# 1S_BATTERY_CHARGER_SCH.net
KiCad netlist of a schematic drawn in Altium Designer
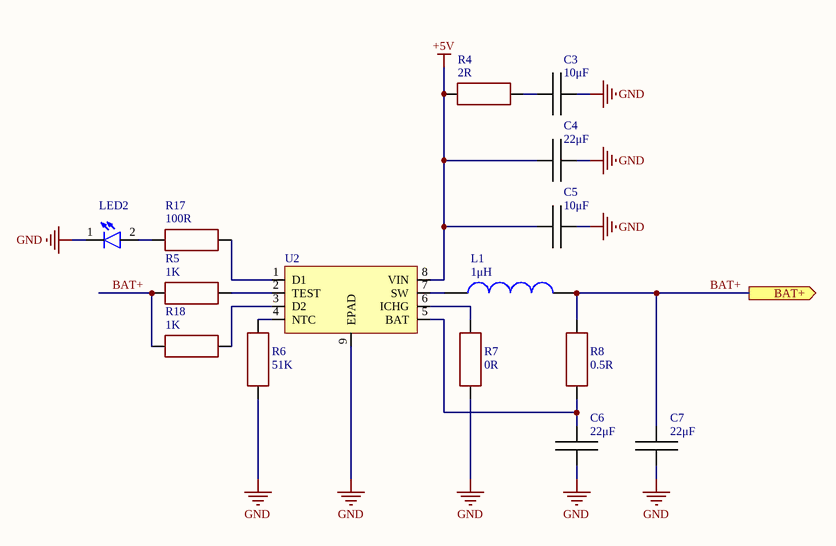
[diagram p0: 1S_BATTERY_CHARGER_SCH.SchDoc]

(export (version "E")
  (design (tool "Eeschema 10.0.6"))
  (components
    (comp (ref "C3")
      (value "10μF")
      (footprint "CAP: 0603")
      (fields (field (name "VOLTAGE") "??V") (field (name "Comment") "Cap_0603"))
      (libsource (lib "capacitor") (part "Cap_0603"))
    )
    (comp (ref "C4")
      (value "22μF")
      (footprint "CAP: 0603")
      (fields (field (name "VOLTAGE") "??V") (field (name "Comment") "Cap_0603"))
      (libsource (lib "capacitor") (part "Cap_0603"))
    )
    (comp (ref "C5")
      (value "10μF")
      (footprint "CAP: 0603")
      (fields (field (name "VOLTAGE") "??V") (field (name "Comment") "Cap_0603"))
      (libsource (lib "capacitor") (part "Cap_0603"))
    )
    (comp (ref "C6")
      (value "22μF")
      (footprint "CAP: 0603")
      (fields (field (name "VOLTAGE") "??V") (field (name "Comment") "Cap_0603"))
      (libsource (lib "capacitor") (part "Cap_0603"))
    )
    (comp (ref "C7")
      (value "22μF")
      (footprint "CAP: 0603")
      (fields (field (name "VOLTAGE") "??V") (field (name "Comment") "Cap_0603"))
      (libsource (lib "capacitor") (part "Cap_0603"))
    )
    (comp (ref "L1")
      (value "1μH")
      (footprint "CDRH74")
      (description "SMD Power Inductor")
      (fields (field (name "MANUFACTURER") "SUMIDA") (field (name "Comment") "CDRH74"))
      (libsource (lib "MY_INT_LIB") (part "CDRH74"))
    )
    (comp (ref "LED2")
      (value "LED_0603")
      (footprint "LED_0603")
      (libsource (lib "MY_INT_LIB") (part "LED_0603"))
    )
    (comp (ref "R4")
      (value "2R")
      (footprint "RES: 0603")
      (fields (field (name "TOLERANCE") "±5%") (field (name "Comment") "Resistor_0603"))
      (libsource (lib "") (part "Resistor_0603_1"))
    )
    (comp (ref "R5")
      (value "1K")
      (footprint "RES: 0603")
      (fields (field (name "TOLERANCE") "±5%") (field (name "Comment") "Resistor_0603"))
      (libsource (lib "resistor") (part "Resistor_0603"))
    )
    (comp (ref "R6")
      (value "51K")
      (footprint "RES: 0603")
      (fields (field (name "TOLERANCE") "±5%") (field (name "Comment") "Resistor_0603"))
      (libsource (lib "") (part "Resistor_0603_1"))
    )
    (comp (ref "R7")
      (value "0R")
      (footprint "RES: 0603")
      (fields (field (name "TOLERANCE") "±5%") (field (name "Comment") "Resistor_0603"))
      (libsource (lib "") (part "Resistor_0603_2"))
    )
    (comp (ref "R8")
      (value "0.5R")
      (footprint "RES: 0603")
      (fields (field (name "TOLERANCE") "±5%") (field (name "Comment") "Resistor_0603"))
      (libsource (lib "") (part "Resistor_0603_1"))
    )
    (comp (ref "R17")
      (value "100R")
      (footprint "RES: 0603")
      (fields (field (name "TOLERANCE") "±5%") (field (name "Comment") "Resistor_0603"))
      (libsource (lib "") (part "Resistor_0603_1"))
    )
    (comp (ref "R18")
      (value "1K")
      (footprint "RES: 0603")
      (fields (field (name "TOLERANCE") "±5%") (field (name "Comment") "Resistor_0603"))
      (libsource (lib "resistor") (part "Resistor_0603"))
    )
    (comp (ref "U2")
      (value "IP2312")
      (footprint "ESOP-8")
      (description "1s charge module")
      (fields (field (name "MANUFACTURER") "INJOINIC"))
      (libsource (lib "MY_INT_LIB") (part "IP2312"))
    )
  )
  (nets
    (net (code "1") (name "+5V") (class "Default")
      (node (ref "C4") (pin "2") (pinfunction "2_2") (pintype "passive"))
      (node (ref "C5") (pin "2") (pinfunction "2_2") (pintype "passive"))
      (node (ref "R4") (pin "1") (pinfunction "1_1") (pintype "passive"))
      (node (ref "U2") (pin "8") (pinfunction "VIN_8") (pintype "passive"))
    )
    (net (code "2") (name "/BAT+") (class "Default")
      (node (ref "C7") (pin "1") (pinfunction "1_1") (pintype "passive"))
      (node (ref "L1") (pin "1") (pinfunction "1_1") (pintype "passive"))
      (node (ref "R18") (pin "1") (pinfunction "1_1") (pintype "passive"))
      (node (ref "R5") (pin "1") (pinfunction "1_1") (pintype "passive"))
      (node (ref "R8") (pin "2") (pinfunction "2_2") (pintype "passive"))
    )
    (net (code "3") (name "GND") (class "Default")
      (node (ref "C3") (pin "1") (pinfunction "1_1") (pintype "passive"))
      (node (ref "C4") (pin "1") (pinfunction "1_1") (pintype "passive"))
      (node (ref "C5") (pin "1") (pinfunction "1_1") (pintype "passive"))
      (node (ref "C6") (pin "2") (pinfunction "2_2") (pintype "passive"))
      (node (ref "C7") (pin "2") (pinfunction "2_2") (pintype "passive"))
      (node (ref "LED2") (pin "1") (pintype "passive"))
      (node (ref "R6") (pin "1") (pinfunction "1_1") (pintype "passive"))
      (node (ref "R7") (pin "2") (pinfunction "2_2") (pintype "passive"))
      (node (ref "U2") (pin "9") (pinfunction "EPAD_9") (pintype "passive"))
    )
    (net (code "4") (name "Net-(C3-Pad2)") (class "Default")
      (node (ref "C3") (pin "2") (pinfunction "2_2") (pintype "passive"))
      (node (ref "R4") (pin "2") (pinfunction "2_2") (pintype "passive"))
    )
    (net (code "5") (name "Net-(LED2-Pad2)") (class "Default")
      (node (ref "LED2") (pin "2") (pintype "passive"))
      (node (ref "R17") (pin "1") (pinfunction "1_1") (pintype "passive"))
    )
    (net (code "6") (name "Net-(U2-BAT)") (class "Default")
      (node (ref "C6") (pin "1") (pinfunction "1_1") (pintype "passive"))
      (node (ref "R8") (pin "1") (pinfunction "1_1") (pintype "passive"))
      (node (ref "U2") (pin "5") (pinfunction "BAT_5") (pintype "passive"))
    )
    (net (code "7") (name "Net-(U2-D1)") (class "Default")
      (node (ref "R17") (pin "2") (pinfunction "2_2") (pintype "passive"))
      (node (ref "U2") (pin "1") (pinfunction "D1_1") (pintype "passive"))
    )
    (net (code "8") (name "Net-(U2-D2)") (class "Default")
      (node (ref "R18") (pin "2") (pinfunction "2_2") (pintype "passive"))
      (node (ref "U2") (pin "3") (pinfunction "D2_3") (pintype "passive"))
    )
    (net (code "9") (name "Net-(U2-ICHG)") (class "Default")
      (node (ref "R7") (pin "1") (pinfunction "1_1") (pintype "passive"))
      (node (ref "U2") (pin "6") (pinfunction "ICHG_6") (pintype "passive"))
    )
    (net (code "10") (name "Net-(U2-NTC)") (class "Default")
      (node (ref "R6") (pin "2") (pinfunction "2_2") (pintype "passive"))
      (node (ref "U2") (pin "4") (pinfunction "NTC_4") (pintype "passive"))
    )
    (net (code "11") (name "Net-(U2-SW)") (class "Default")
      (node (ref "L1") (pin "2") (pinfunction "2_2") (pintype "passive"))
      (node (ref "U2") (pin "7") (pinfunction "SW_7") (pintype "passive"))
    )
    (net (code "12") (name "Net-(U2-TEST)") (class "Default")
      (node (ref "R5") (pin "2") (pinfunction "2_2") (pintype "passive"))
      (node (ref "U2") (pin "2") (pinfunction "TEST_2") (pintype "passive"))
    )
  )
)
